# halo_244.net
KiCad netlist of a schematic drawn in EAGLE
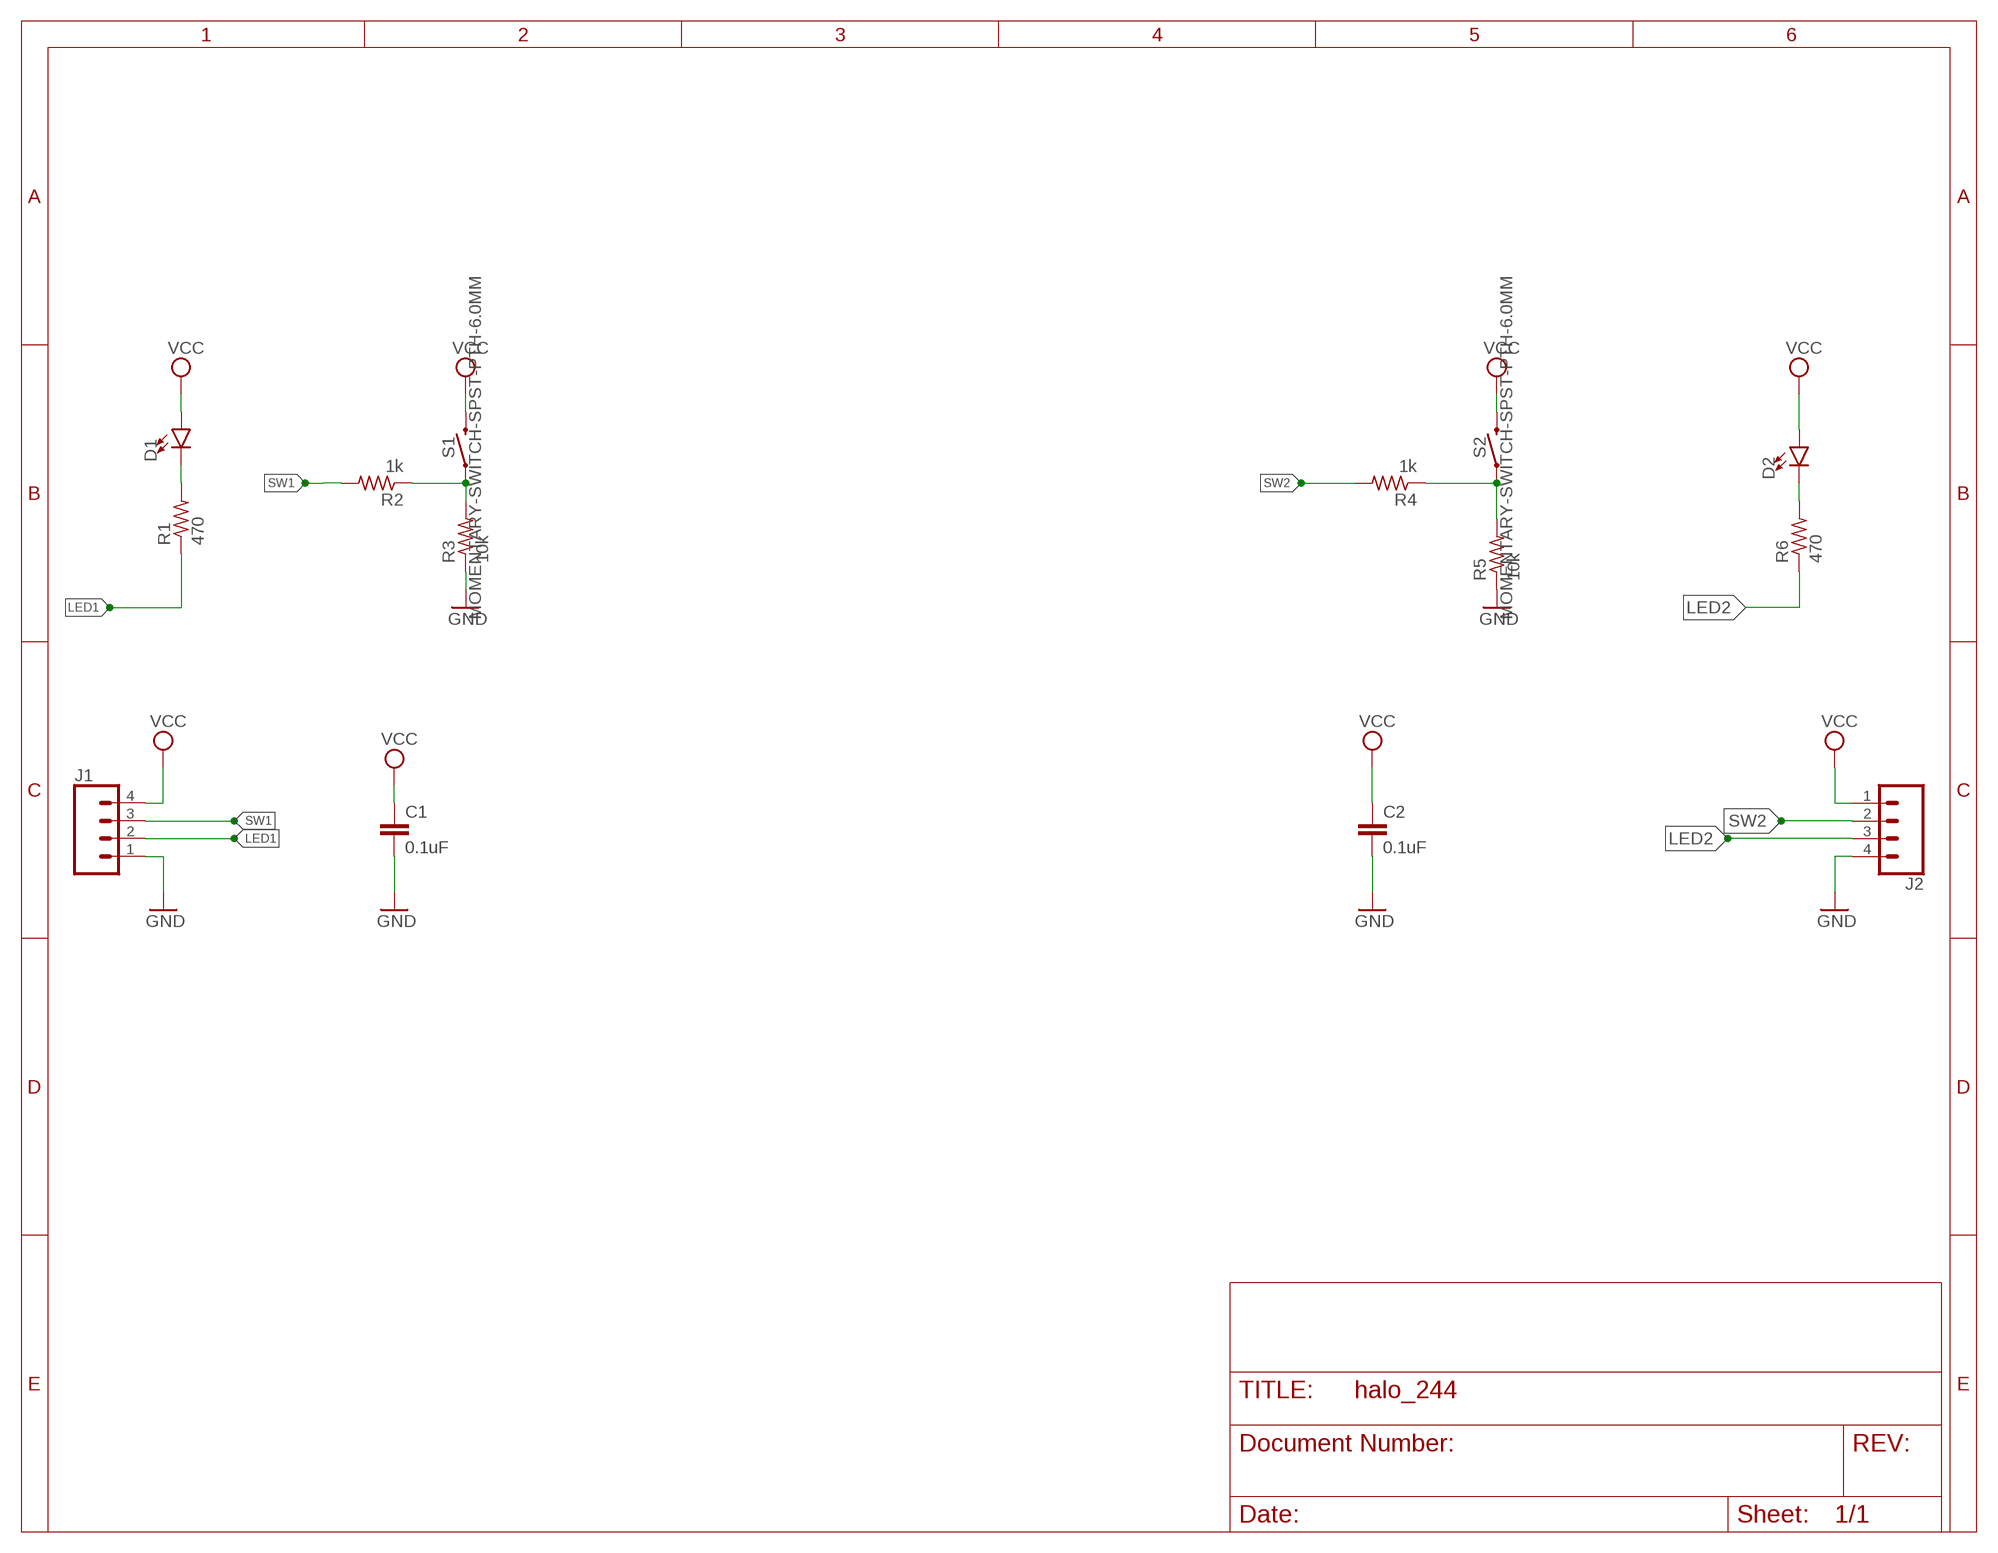
[diagram p0: schematic, sheet 1]

(export (version "E")
  (design (tool "Eeschema 10.0.6"))
  (components
    (comp (ref "C1")
      (value "0.1uF")
      (footprint "eagle-import:CAP-PTH-SMALL-KIT")
      (libsource (lib "eagle-import") (part "0.1UF-KIT-EZ-50V-20%"))
    )
    (comp (ref "C2")
      (value "0.1uF")
      (footprint "eagle-import:CAP-PTH-SMALL-KIT")
      (libsource (lib "eagle-import") (part "0.1UF-KIT-EZ-50V-20%"))
    )
    (comp (ref "D1")
      (value "LED-3MM-NO_SILK")
      (footprint "eagle-import:LED_3MM-NS")
      (libsource (lib "eagle-import") (part "LED-3MM-NO_SILK"))
    )
    (comp (ref "D2")
      (value "LED-3MM-NO_SILK")
      (footprint "eagle-import:LED_3MM-NS")
      (libsource (lib "eagle-import") (part "LED-3MM-NO_SILK"))
    )
    (comp (ref "J1")
      (value "CONN_04")
      (footprint "eagle-import:1X04")
      (libsource (lib "eagle-import") (part "CONN_04"))
    )
    (comp (ref "J2")
      (value "CONN_04")
      (footprint "eagle-import:1X04")
      (libsource (lib "eagle-import") (part "CONN_04"))
    )
    (comp (ref "R1")
      (value "470")
      (footprint "eagle-import:0207_12")
      (fields (field (name "MF") "FARNELL") (field (name "MPN") "MCF 0.25W 470R"))
      (libsource (lib "eagle-import") (part "R-US_0207/12"))
    )
    (comp (ref "R2")
      (value "1k")
      (footprint "eagle-import:0207_12")
      (libsource (lib "eagle-import") (part "R-US_0207/12"))
    )
    (comp (ref "R3")
      (value "10k")
      (footprint "eagle-import:0207_12")
      (fields (field (name "MF") "FARNELL") (field (name "MPN") "MCF 0.25W 10K"))
      (libsource (lib "eagle-import") (part "R-US_0207/12"))
    )
    (comp (ref "R4")
      (value "1k")
      (footprint "eagle-import:0207_12")
      (libsource (lib "eagle-import") (part "R-US_0207/12"))
    )
    (comp (ref "R5")
      (value "10k")
      (footprint "eagle-import:0207_12")
      (fields (field (name "MF") "FARNELL") (field (name "MPN") "MCF 0.25W 10K"))
      (libsource (lib "eagle-import") (part "R-US_0207/12"))
    )
    (comp (ref "R6")
      (value "470")
      (footprint "eagle-import:0207_12")
      (fields (field (name "MF") "FARNELL") (field (name "MPN") "MCF 0.25W 470R"))
      (libsource (lib "eagle-import") (part "R-US_0207/12"))
    )
    (comp (ref "S1")
      (value "MOMENTARY-SWITCH-SPST-PTH-6.0MM")
      (footprint "eagle-import:TACTILE_SWITCH_PTH_6.0MM")
      (libsource (lib "eagle-import") (part "MOMENTARY-SWITCH-SPST-PTH-6.0MM"))
    )
    (comp (ref "S2")
      (value "MOMENTARY-SWITCH-SPST-PTH-6.0MM")
      (footprint "eagle-import:TACTILE_SWITCH_PTH_6.0MM")
      (libsource (lib "eagle-import") (part "MOMENTARY-SWITCH-SPST-PTH-6.0MM"))
    )
  )
  (nets
    (net (code "1") (name "GND") (class "Default")
      (node (ref "C1") (pin "2") (pinfunction "2_2") (pintype "passive"))
      (node (ref "C2") (pin "2") (pinfunction "2_2") (pintype "passive"))
      (node (ref "J1") (pin "1") (pinfunction "1_1") (pintype "passive"))
      (node (ref "J2") (pin "4") (pinfunction "4_4") (pintype "passive"))
      (node (ref "R3") (pin "1") (pinfunction "1_1") (pintype "passive"))
      (node (ref "R5") (pin "1") (pinfunction "1_1") (pintype "passive"))
    )
    (net (code "2") (name "LED1") (class "Default")
      (node (ref "J1") (pin "2") (pinfunction "2_2") (pintype "passive"))
      (node (ref "R1") (pin "1") (pinfunction "1_1") (pintype "passive"))
    )
    (net (code "3") (name "LED2") (class "Default")
      (node (ref "J2") (pin "3") (pinfunction "3_3") (pintype "passive"))
      (node (ref "R6") (pin "1") (pinfunction "1_1") (pintype "passive"))
    )
    (net (code "4") (name "Net-(D1-C)") (class "Default")
      (node (ref "D1") (pin "K") (pinfunction "C_K") (pintype "passive"))
      (node (ref "R1") (pin "2") (pinfunction "2_2") (pintype "passive"))
    )
    (net (code "5") (name "Net-(D2-C)") (class "Default")
      (node (ref "D2") (pin "K") (pinfunction "C_K") (pintype "passive"))
      (node (ref "R6") (pin "2") (pinfunction "2_2") (pintype "passive"))
    )
    (net (code "6") (name "Net-(R2-Pad1)") (class "Default")
      (node (ref "R2") (pin "1") (pinfunction "1_1") (pintype "passive"))
      (node (ref "R3") (pin "2") (pinfunction "2_2") (pintype "passive"))
      (node (ref "S1") (pin "1") (pinfunction "1_1") (pintype "passive"))
    )
    (net (code "7") (name "Net-(R4-Pad1)") (class "Default")
      (node (ref "R4") (pin "1") (pinfunction "1_1") (pintype "passive"))
      (node (ref "R5") (pin "2") (pinfunction "2_2") (pintype "passive"))
      (node (ref "S2") (pin "1") (pinfunction "1_1") (pintype "passive"))
    )
    (net (code "8") (name "SW1") (class "Default")
      (node (ref "J1") (pin "3") (pinfunction "3_3") (pintype "passive"))
      (node (ref "R2") (pin "2") (pinfunction "2_2") (pintype "passive"))
    )
    (net (code "9") (name "SW2") (class "Default")
      (node (ref "J2") (pin "2") (pinfunction "2_2") (pintype "passive"))
      (node (ref "R4") (pin "2") (pinfunction "2_2") (pintype "passive"))
    )
    (net (code "10") (name "VCC") (class "Default")
      (node (ref "C1") (pin "1") (pinfunction "1_1") (pintype "passive"))
      (node (ref "C2") (pin "1") (pinfunction "1_1") (pintype "passive"))
      (node (ref "D1") (pin "A") (pinfunction "A_A") (pintype "passive"))
      (node (ref "D2") (pin "A") (pinfunction "A_A") (pintype "passive"))
      (node (ref "J1") (pin "4") (pinfunction "4_4") (pintype "passive"))
      (node (ref "J2") (pin "1") (pinfunction "1_1") (pintype "passive"))
      (node (ref "S1") (pin "3") (pinfunction "2_3") (pintype "passive"))
      (node (ref "S2") (pin "3") (pinfunction "2_3") (pintype "passive"))
    )
  )
)
